# ws2812.net
KiCad netlist of a schematic drawn in Altium Designer
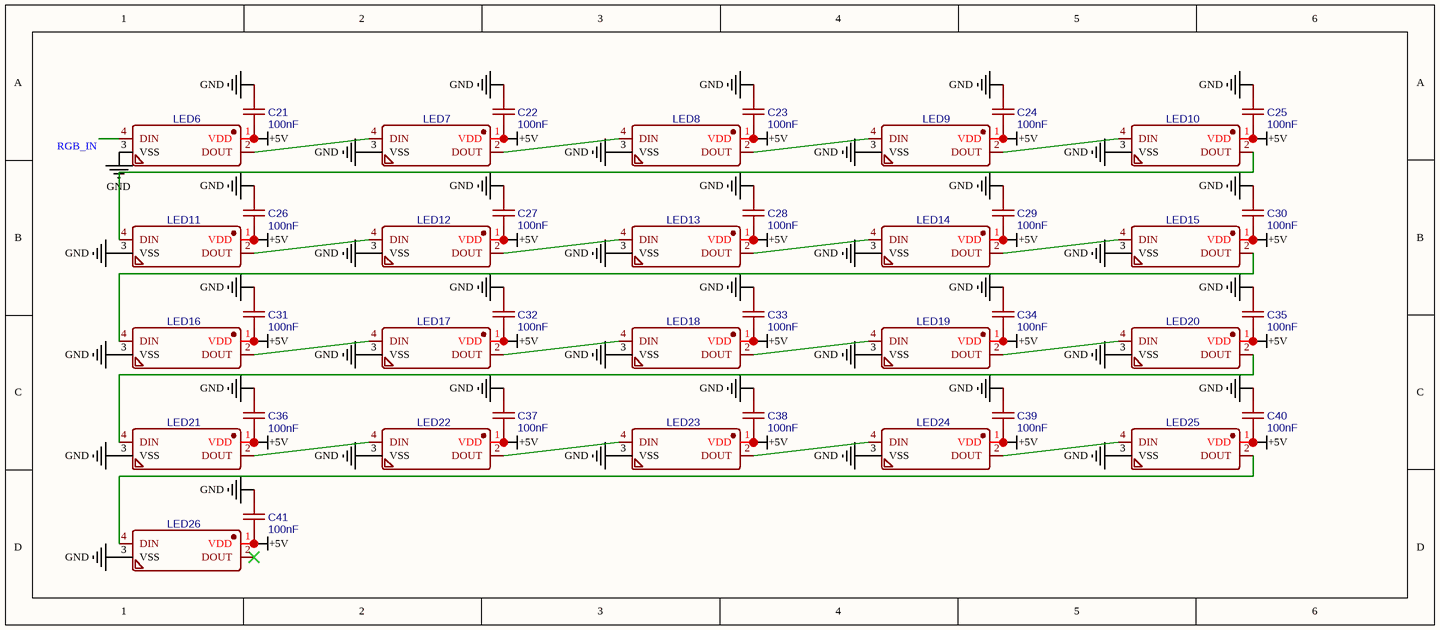
[diagram p0: ws2812.schdoc]

(export (version "E")
  (design (tool "Eeschema 10.0.6"))
  (components
    (comp (ref "C21")
      (value "100nF")
      (fields
        (field (name "BOM_MANUFACTURER PART") "CC0603KRX7R9BB104")
        (field (name "BOM_SUPPLIER PART") "C14663")
      )
      (libsource (lib "altium-import") (part "root_3_100nF_"))
    )
    (comp (ref "C22")
      (value "100nF")
      (fields
        (field (name "BOM_MANUFACTURER PART") "CC0603KRX7R9BB104")
        (field (name "BOM_SUPPLIER PART") "C14663")
      )
      (libsource (lib "altium-import") (part "root_3_100nF_"))
    )
    (comp (ref "C23")
      (value "100nF")
      (fields
        (field (name "BOM_MANUFACTURER PART") "CC0603KRX7R9BB104")
        (field (name "BOM_SUPPLIER PART") "C14663")
      )
      (libsource (lib "altium-import") (part "root_3_100nF_"))
    )
    (comp (ref "C24")
      (value "100nF")
      (fields
        (field (name "BOM_MANUFACTURER PART") "CC0603KRX7R9BB104")
        (field (name "BOM_SUPPLIER PART") "C14663")
      )
      (libsource (lib "altium-import") (part "root_3_100nF_"))
    )
    (comp (ref "C25")
      (value "100nF")
      (fields
        (field (name "BOM_MANUFACTURER PART") "CC0603KRX7R9BB104")
        (field (name "BOM_SUPPLIER PART") "C14663")
      )
      (libsource (lib "altium-import") (part "root_3_100nF_"))
    )
    (comp (ref "C26")
      (value "100nF")
      (fields
        (field (name "BOM_MANUFACTURER PART") "CC0603KRX7R9BB104")
        (field (name "BOM_SUPPLIER PART") "C14663")
      )
      (libsource (lib "altium-import") (part "root_3_100nF_"))
    )
    (comp (ref "C27")
      (value "100nF")
      (fields
        (field (name "BOM_MANUFACTURER PART") "CC0603KRX7R9BB104")
        (field (name "BOM_SUPPLIER PART") "C14663")
      )
      (libsource (lib "altium-import") (part "root_3_100nF_"))
    )
    (comp (ref "C28")
      (value "100nF")
      (fields
        (field (name "BOM_MANUFACTURER PART") "CC0603KRX7R9BB104")
        (field (name "BOM_SUPPLIER PART") "C14663")
      )
      (libsource (lib "altium-import") (part "root_3_100nF_"))
    )
    (comp (ref "C29")
      (value "100nF")
      (fields
        (field (name "BOM_MANUFACTURER PART") "CC0603KRX7R9BB104")
        (field (name "BOM_SUPPLIER PART") "C14663")
      )
      (libsource (lib "altium-import") (part "root_3_100nF_"))
    )
    (comp (ref "C30")
      (value "100nF")
      (fields
        (field (name "BOM_MANUFACTURER PART") "CC0603KRX7R9BB104")
        (field (name "BOM_SUPPLIER PART") "C14663")
      )
      (libsource (lib "altium-import") (part "root_3_100nF_"))
    )
    (comp (ref "C31")
      (value "100nF")
      (fields
        (field (name "BOM_MANUFACTURER PART") "CC0603KRX7R9BB104")
        (field (name "BOM_SUPPLIER PART") "C14663")
      )
      (libsource (lib "altium-import") (part "root_3_100nF_"))
    )
    (comp (ref "C32")
      (value "100nF")
      (fields
        (field (name "BOM_MANUFACTURER PART") "CC0603KRX7R9BB104")
        (field (name "BOM_SUPPLIER PART") "C14663")
      )
      (libsource (lib "altium-import") (part "root_3_100nF_"))
    )
    (comp (ref "C33")
      (value "100nF")
      (fields
        (field (name "BOM_MANUFACTURER PART") "CC0603KRX7R9BB104")
        (field (name "BOM_SUPPLIER PART") "C14663")
      )
      (libsource (lib "altium-import") (part "root_3_100nF_"))
    )
    (comp (ref "C34")
      (value "100nF")
      (fields
        (field (name "BOM_MANUFACTURER PART") "CC0603KRX7R9BB104")
        (field (name "BOM_SUPPLIER PART") "C14663")
      )
      (libsource (lib "altium-import") (part "root_3_100nF_"))
    )
    (comp (ref "C35")
      (value "100nF")
      (fields
        (field (name "BOM_MANUFACTURER PART") "CC0603KRX7R9BB104")
        (field (name "BOM_SUPPLIER PART") "C14663")
      )
      (libsource (lib "altium-import") (part "root_3_100nF_"))
    )
    (comp (ref "C36")
      (value "100nF")
      (fields
        (field (name "BOM_MANUFACTURER PART") "CC0603KRX7R9BB104")
        (field (name "BOM_SUPPLIER PART") "C14663")
      )
      (libsource (lib "altium-import") (part "root_3_100nF_"))
    )
    (comp (ref "C37")
      (value "100nF")
      (fields
        (field (name "BOM_MANUFACTURER PART") "CC0603KRX7R9BB104")
        (field (name "BOM_SUPPLIER PART") "C14663")
      )
      (libsource (lib "altium-import") (part "root_3_100nF_"))
    )
    (comp (ref "C38")
      (value "100nF")
      (fields
        (field (name "BOM_MANUFACTURER PART") "CC0603KRX7R9BB104")
        (field (name "BOM_SUPPLIER PART") "C14663")
      )
      (libsource (lib "altium-import") (part "root_3_100nF_"))
    )
    (comp (ref "C39")
      (value "100nF")
      (fields
        (field (name "BOM_MANUFACTURER PART") "CC0603KRX7R9BB104")
        (field (name "BOM_SUPPLIER PART") "C14663")
      )
      (libsource (lib "altium-import") (part "root_3_100nF_"))
    )
    (comp (ref "C40")
      (value "100nF")
      (fields
        (field (name "BOM_MANUFACTURER PART") "CC0603KRX7R9BB104")
        (field (name "BOM_SUPPLIER PART") "C14663")
      )
      (libsource (lib "altium-import") (part "root_3_100nF_"))
    )
    (comp (ref "C41")
      (value "100nF")
      (fields
        (field (name "BOM_MANUFACTURER PART") "CC0603KRX7R9BB104")
        (field (name "BOM_SUPPLIER PART") "C14663")
      )
      (libsource (lib "altium-import") (part "root_3_100nF_"))
    )
    (comp (ref "LED6")
      (value "WS2812E")
      (fields (field (name "BOM_SUPPLIER PART") "C139127") (field (name "CONTRIBUTOR") "LCSC"))
      (libsource (lib "altium-import") (part "root_0_WS2812E_"))
    )
    (comp (ref "LED7")
      (value "WS2812E")
      (fields (field (name "BOM_SUPPLIER PART") "C139127") (field (name "CONTRIBUTOR") "LCSC"))
      (libsource (lib "altium-import") (part "root_0_WS2812E_"))
    )
    (comp (ref "LED8")
      (value "WS2812E")
      (fields (field (name "BOM_SUPPLIER PART") "C139127") (field (name "CONTRIBUTOR") "LCSC"))
      (libsource (lib "altium-import") (part "root_0_WS2812E_"))
    )
    (comp (ref "LED9")
      (value "WS2812E")
      (fields (field (name "BOM_SUPPLIER PART") "C139127") (field (name "CONTRIBUTOR") "LCSC"))
      (libsource (lib "altium-import") (part "root_0_WS2812E_"))
    )
    (comp (ref "LED10")
      (value "WS2812E")
      (fields (field (name "BOM_SUPPLIER PART") "C139127") (field (name "CONTRIBUTOR") "LCSC"))
      (libsource (lib "altium-import") (part "root_0_WS2812E_"))
    )
    (comp (ref "LED11")
      (value "WS2812E")
      (fields (field (name "BOM_SUPPLIER PART") "C139127") (field (name "CONTRIBUTOR") "LCSC"))
      (libsource (lib "altium-import") (part "root_0_WS2812E_"))
    )
    (comp (ref "LED12")
      (value "WS2812E")
      (fields (field (name "BOM_SUPPLIER PART") "C139127") (field (name "CONTRIBUTOR") "LCSC"))
      (libsource (lib "altium-import") (part "root_0_WS2812E_"))
    )
    (comp (ref "LED13")
      (value "WS2812E")
      (fields (field (name "BOM_SUPPLIER PART") "C139127") (field (name "CONTRIBUTOR") "LCSC"))
      (libsource (lib "altium-import") (part "root_0_WS2812E_"))
    )
    (comp (ref "LED14")
      (value "WS2812E")
      (fields (field (name "BOM_SUPPLIER PART") "C139127") (field (name "CONTRIBUTOR") "LCSC"))
      (libsource (lib "altium-import") (part "root_0_WS2812E_"))
    )
    (comp (ref "LED15")
      (value "WS2812E")
      (fields (field (name "BOM_SUPPLIER PART") "C139127") (field (name "CONTRIBUTOR") "LCSC"))
      (libsource (lib "altium-import") (part "root_0_WS2812E_"))
    )
    (comp (ref "LED16")
      (value "WS2812E")
      (fields (field (name "BOM_SUPPLIER PART") "C139127") (field (name "CONTRIBUTOR") "LCSC"))
      (libsource (lib "altium-import") (part "root_0_WS2812E_"))
    )
    (comp (ref "LED17")
      (value "WS2812E")
      (fields (field (name "BOM_SUPPLIER PART") "C139127") (field (name "CONTRIBUTOR") "LCSC"))
      (libsource (lib "altium-import") (part "root_0_WS2812E_"))
    )
    (comp (ref "LED18")
      (value "WS2812E")
      (fields (field (name "BOM_SUPPLIER PART") "C139127") (field (name "CONTRIBUTOR") "LCSC"))
      (libsource (lib "altium-import") (part "root_0_WS2812E_"))
    )
    (comp (ref "LED19")
      (value "WS2812E")
      (fields (field (name "BOM_SUPPLIER PART") "C139127") (field (name "CONTRIBUTOR") "LCSC"))
      (libsource (lib "altium-import") (part "root_0_WS2812E_"))
    )
    (comp (ref "LED20")
      (value "WS2812E")
      (fields (field (name "BOM_SUPPLIER PART") "C139127") (field (name "CONTRIBUTOR") "LCSC"))
      (libsource (lib "altium-import") (part "root_0_WS2812E_"))
    )
    (comp (ref "LED21")
      (value "WS2812E")
      (fields (field (name "BOM_SUPPLIER PART") "C139127") (field (name "CONTRIBUTOR") "LCSC"))
      (libsource (lib "altium-import") (part "root_0_WS2812E_"))
    )
    (comp (ref "LED22")
      (value "WS2812E")
      (fields (field (name "BOM_SUPPLIER PART") "C139127") (field (name "CONTRIBUTOR") "LCSC"))
      (libsource (lib "altium-import") (part "root_0_WS2812E_"))
    )
    (comp (ref "LED23")
      (value "WS2812E")
      (fields (field (name "BOM_SUPPLIER PART") "C139127") (field (name "CONTRIBUTOR") "LCSC"))
      (libsource (lib "altium-import") (part "root_0_WS2812E_"))
    )
    (comp (ref "LED24")
      (value "WS2812E")
      (fields (field (name "BOM_SUPPLIER PART") "C139127") (field (name "CONTRIBUTOR") "LCSC"))
      (libsource (lib "altium-import") (part "root_0_WS2812E_"))
    )
    (comp (ref "LED25")
      (value "WS2812E")
      (fields (field (name "BOM_SUPPLIER PART") "C139127") (field (name "CONTRIBUTOR") "LCSC"))
      (libsource (lib "altium-import") (part "root_0_WS2812E_"))
    )
    (comp (ref "LED26")
      (value "WS2812E")
      (fields (field (name "BOM_SUPPLIER PART") "C139127") (field (name "CONTRIBUTOR") "LCSC"))
      (libsource (lib "altium-import") (part "root_0_WS2812E_"))
    )
  )
  (nets
    (net (code "1") (name "+5V") (class "Default")
      (node (ref "C21") (pin "2") (pinfunction "2_2") (pintype "passive"))
      (node (ref "C22") (pin "2") (pinfunction "2_2") (pintype "passive"))
      (node (ref "C23") (pin "2") (pinfunction "2_2") (pintype "passive"))
      (node (ref "C24") (pin "2") (pinfunction "2_2") (pintype "passive"))
      (node (ref "C25") (pin "2") (pinfunction "2_2") (pintype "passive"))
      (node (ref "C26") (pin "2") (pinfunction "2_2") (pintype "passive"))
      (node (ref "C27") (pin "2") (pinfunction "2_2") (pintype "passive"))
      (node (ref "C28") (pin "2") (pinfunction "2_2") (pintype "passive"))
      (node (ref "C29") (pin "2") (pinfunction "2_2") (pintype "passive"))
      (node (ref "C30") (pin "2") (pinfunction "2_2") (pintype "passive"))
      (node (ref "C31") (pin "2") (pinfunction "2_2") (pintype "passive"))
      (node (ref "C32") (pin "2") (pinfunction "2_2") (pintype "passive"))
      (node (ref "C33") (pin "2") (pinfunction "2_2") (pintype "passive"))
      (node (ref "C34") (pin "2") (pinfunction "2_2") (pintype "passive"))
      (node (ref "C35") (pin "2") (pinfunction "2_2") (pintype "passive"))
      (node (ref "C36") (pin "2") (pinfunction "2_2") (pintype "passive"))
      (node (ref "C37") (pin "2") (pinfunction "2_2") (pintype "passive"))
      (node (ref "C38") (pin "2") (pinfunction "2_2") (pintype "passive"))
      (node (ref "C39") (pin "2") (pinfunction "2_2") (pintype "passive"))
      (node (ref "C40") (pin "2") (pinfunction "2_2") (pintype "passive"))
      (node (ref "C41") (pin "2") (pinfunction "2_2") (pintype "passive"))
      (node (ref "LED10") (pin "1") (pinfunction "VDD_1") (pintype "passive"))
      (node (ref "LED11") (pin "1") (pinfunction "VDD_1") (pintype "passive"))
      (node (ref "LED12") (pin "1") (pinfunction "VDD_1") (pintype "passive"))
      (node (ref "LED13") (pin "1") (pinfunction "VDD_1") (pintype "passive"))
      (node (ref "LED14") (pin "1") (pinfunction "VDD_1") (pintype "passive"))
      (node (ref "LED15") (pin "1") (pinfunction "VDD_1") (pintype "passive"))
      (node (ref "LED16") (pin "1") (pinfunction "VDD_1") (pintype "passive"))
      (node (ref "LED17") (pin "1") (pinfunction "VDD_1") (pintype "passive"))
      (node (ref "LED18") (pin "1") (pinfunction "VDD_1") (pintype "passive"))
      (node (ref "LED19") (pin "1") (pinfunction "VDD_1") (pintype "passive"))
      (node (ref "LED20") (pin "1") (pinfunction "VDD_1") (pintype "passive"))
      (node (ref "LED21") (pin "1") (pinfunction "VDD_1") (pintype "passive"))
      (node (ref "LED22") (pin "1") (pinfunction "VDD_1") (pintype "passive"))
      (node (ref "LED23") (pin "1") (pinfunction "VDD_1") (pintype "passive"))
      (node (ref "LED24") (pin "1") (pinfunction "VDD_1") (pintype "passive"))
      (node (ref "LED25") (pin "1") (pinfunction "VDD_1") (pintype "passive"))
      (node (ref "LED26") (pin "1") (pinfunction "VDD_1") (pintype "passive"))
      (node (ref "LED6") (pin "1") (pinfunction "VDD_1") (pintype "passive"))
      (node (ref "LED7") (pin "1") (pinfunction "VDD_1") (pintype "passive"))
      (node (ref "LED8") (pin "1") (pinfunction "VDD_1") (pintype "passive"))
      (node (ref "LED9") (pin "1") (pinfunction "VDD_1") (pintype "passive"))
    )
    (net (code "2") (name "/RGB_IN") (class "Default")
      (node (ref "LED6") (pin "4") (pinfunction "DIN_4") (pintype "passive"))
    )
    (net (code "3") (name "GND") (class "Default")
      (node (ref "C21") (pin "1") (pinfunction "1_1") (pintype "passive"))
      (node (ref "C22") (pin "1") (pinfunction "1_1") (pintype "passive"))
      (node (ref "C23") (pin "1") (pinfunction "1_1") (pintype "passive"))
      (node (ref "C24") (pin "1") (pinfunction "1_1") (pintype "passive"))
      (node (ref "C25") (pin "1") (pinfunction "1_1") (pintype "passive"))
      (node (ref "C26") (pin "1") (pinfunction "1_1") (pintype "passive"))
      (node (ref "C27") (pin "1") (pinfunction "1_1") (pintype "passive"))
      (node (ref "C28") (pin "1") (pinfunction "1_1") (pintype "passive"))
      (node (ref "C29") (pin "1") (pinfunction "1_1") (pintype "passive"))
      (node (ref "C30") (pin "1") (pinfunction "1_1") (pintype "passive"))
      (node (ref "C31") (pin "1") (pinfunction "1_1") (pintype "passive"))
      (node (ref "C32") (pin "1") (pinfunction "1_1") (pintype "passive"))
      (node (ref "C33") (pin "1") (pinfunction "1_1") (pintype "passive"))
      (node (ref "C34") (pin "1") (pinfunction "1_1") (pintype "passive"))
      (node (ref "C35") (pin "1") (pinfunction "1_1") (pintype "passive"))
      (node (ref "C36") (pin "1") (pinfunction "1_1") (pintype "passive"))
      (node (ref "C37") (pin "1") (pinfunction "1_1") (pintype "passive"))
      (node (ref "C38") (pin "1") (pinfunction "1_1") (pintype "passive"))
      (node (ref "C39") (pin "1") (pinfunction "1_1") (pintype "passive"))
      (node (ref "C40") (pin "1") (pinfunction "1_1") (pintype "passive"))
      (node (ref "C41") (pin "1") (pinfunction "1_1") (pintype "passive"))
      (node (ref "LED10") (pin "3") (pinfunction "VSS_3") (pintype "passive"))
      (node (ref "LED11") (pin "3") (pinfunction "VSS_3") (pintype "passive"))
      (node (ref "LED12") (pin "3") (pinfunction "VSS_3") (pintype "passive"))
      (node (ref "LED13") (pin "3") (pinfunction "VSS_3") (pintype "passive"))
      (node (ref "LED14") (pin "3") (pinfunction "VSS_3") (pintype "passive"))
      (node (ref "LED15") (pin "3") (pinfunction "VSS_3") (pintype "passive"))
      (node (ref "LED16") (pin "3") (pinfunction "VSS_3") (pintype "passive"))
      (node (ref "LED17") (pin "3") (pinfunction "VSS_3") (pintype "passive"))
      (node (ref "LED18") (pin "3") (pinfunction "VSS_3") (pintype "passive"))
      (node (ref "LED19") (pin "3") (pinfunction "VSS_3") (pintype "passive"))
      (node (ref "LED20") (pin "3") (pinfunction "VSS_3") (pintype "passive"))
      (node (ref "LED21") (pin "3") (pinfunction "VSS_3") (pintype "passive"))
      (node (ref "LED22") (pin "3") (pinfunction "VSS_3") (pintype "passive"))
      (node (ref "LED23") (pin "3") (pinfunction "VSS_3") (pintype "passive"))
      (node (ref "LED24") (pin "3") (pinfunction "VSS_3") (pintype "passive"))
      (node (ref "LED25") (pin "3") (pinfunction "VSS_3") (pintype "passive"))
      (node (ref "LED26") (pin "3") (pinfunction "VSS_3") (pintype "passive"))
      (node (ref "LED6") (pin "3") (pinfunction "VSS_3") (pintype "passive"))
      (node (ref "LED7") (pin "3") (pinfunction "VSS_3") (pintype "passive"))
      (node (ref "LED8") (pin "3") (pinfunction "VSS_3") (pintype "passive"))
      (node (ref "LED9") (pin "3") (pinfunction "VSS_3") (pintype "passive"))
    )
    (net (code "4") (name "Net-(LED6-DOUT)") (class "Default")
      (node (ref "LED6") (pin "2") (pinfunction "DOUT_2") (pintype "passive"))
      (node (ref "LED7") (pin "4") (pinfunction "DIN_4") (pintype "passive"))
    )
    (net (code "5") (name "Net-(LED7-DOUT)") (class "Default")
      (node (ref "LED7") (pin "2") (pinfunction "DOUT_2") (pintype "passive"))
      (node (ref "LED8") (pin "4") (pinfunction "DIN_4") (pintype "passive"))
    )
    (net (code "6") (name "Net-(LED8-DOUT)") (class "Default")
      (node (ref "LED8") (pin "2") (pinfunction "DOUT_2") (pintype "passive"))
      (node (ref "LED9") (pin "4") (pinfunction "DIN_4") (pintype "passive"))
    )
    (net (code "7") (name "Net-(LED10-DIN)") (class "Default")
      (node (ref "LED10") (pin "4") (pinfunction "DIN_4") (pintype "passive"))
      (node (ref "LED9") (pin "2") (pinfunction "DOUT_2") (pintype "passive"))
    )
    (net (code "8") (name "Net-(LED10-DOUT)") (class "Default")
      (node (ref "LED10") (pin "2") (pinfunction "DOUT_2") (pintype "passive"))
      (node (ref "LED11") (pin "4") (pinfunction "DIN_4") (pintype "passive"))
    )
    (net (code "9") (name "Net-(LED11-DOUT)") (class "Default")
      (node (ref "LED11") (pin "2") (pinfunction "DOUT_2") (pintype "passive"))
      (node (ref "LED12") (pin "4") (pinfunction "DIN_4") (pintype "passive"))
    )
    (net (code "10") (name "Net-(LED12-DOUT)") (class "Default")
      (node (ref "LED12") (pin "2") (pinfunction "DOUT_2") (pintype "passive"))
      (node (ref "LED13") (pin "4") (pinfunction "DIN_4") (pintype "passive"))
    )
    (net (code "11") (name "Net-(LED13-DOUT)") (class "Default")
      (node (ref "LED13") (pin "2") (pinfunction "DOUT_2") (pintype "passive"))
      (node (ref "LED14") (pin "4") (pinfunction "DIN_4") (pintype "passive"))
    )
    (net (code "12") (name "Net-(LED14-DOUT)") (class "Default")
      (node (ref "LED14") (pin "2") (pinfunction "DOUT_2") (pintype "passive"))
      (node (ref "LED15") (pin "4") (pinfunction "DIN_4") (pintype "passive"))
    )
    (net (code "13") (name "Net-(LED15-DOUT)") (class "Default")
      (node (ref "LED15") (pin "2") (pinfunction "DOUT_2") (pintype "passive"))
      (node (ref "LED16") (pin "4") (pinfunction "DIN_4") (pintype "passive"))
    )
    (net (code "14") (name "Net-(LED16-DOUT)") (class "Default")
      (node (ref "LED16") (pin "2") (pinfunction "DOUT_2") (pintype "passive"))
      (node (ref "LED17") (pin "4") (pinfunction "DIN_4") (pintype "passive"))
    )
    (net (code "15") (name "Net-(LED17-DOUT)") (class "Default")
      (node (ref "LED17") (pin "2") (pinfunction "DOUT_2") (pintype "passive"))
      (node (ref "LED18") (pin "4") (pinfunction "DIN_4") (pintype "passive"))
    )
    (net (code "16") (name "Net-(LED18-DOUT)") (class "Default")
      (node (ref "LED18") (pin "2") (pinfunction "DOUT_2") (pintype "passive"))
      (node (ref "LED19") (pin "4") (pinfunction "DIN_4") (pintype "passive"))
    )
    (net (code "17") (name "Net-(LED19-DOUT)") (class "Default")
      (node (ref "LED19") (pin "2") (pinfunction "DOUT_2") (pintype "passive"))
      (node (ref "LED20") (pin "4") (pinfunction "DIN_4") (pintype "passive"))
    )
    (net (code "18") (name "Net-(LED20-DOUT)") (class "Default")
      (node (ref "LED20") (pin "2") (pinfunction "DOUT_2") (pintype "passive"))
      (node (ref "LED21") (pin "4") (pinfunction "DIN_4") (pintype "passive"))
    )
    (net (code "19") (name "Net-(LED21-DOUT)") (class "Default")
      (node (ref "LED21") (pin "2") (pinfunction "DOUT_2") (pintype "passive"))
      (node (ref "LED22") (pin "4") (pinfunction "DIN_4") (pintype "passive"))
    )
    (net (code "20") (name "Net-(LED22-DOUT)") (class "Default")
      (node (ref "LED22") (pin "2") (pinfunction "DOUT_2") (pintype "passive"))
      (node (ref "LED23") (pin "4") (pinfunction "DIN_4") (pintype "passive"))
    )
    (net (code "21") (name "Net-(LED23-DOUT)") (class "Default")
      (node (ref "LED23") (pin "2") (pinfunction "DOUT_2") (pintype "passive"))
      (node (ref "LED24") (pin "4") (pinfunction "DIN_4") (pintype "passive"))
    )
    (net (code "22") (name "Net-(LED24-DOUT)") (class "Default")
      (node (ref "LED24") (pin "2") (pinfunction "DOUT_2") (pintype "passive"))
      (node (ref "LED25") (pin "4") (pinfunction "DIN_4") (pintype "passive"))
    )
    (net (code "23") (name "Net-(LED25-DOUT)") (class "Default")
      (node (ref "LED25") (pin "2") (pinfunction "DOUT_2") (pintype "passive"))
      (node (ref "LED26") (pin "4") (pinfunction "DIN_4") (pintype "passive"))
    )
    (net (code "24") (name "unconnected-(LED26-DOUT-Pad2)") (class "Default")
      (node (ref "LED26") (pin "2") (pinfunction "DOUT_2") (pintype "passive+no_connect"))
    )
  )
)
